# HDMI.net
KiCad netlist of a schematic drawn in Altium Designer
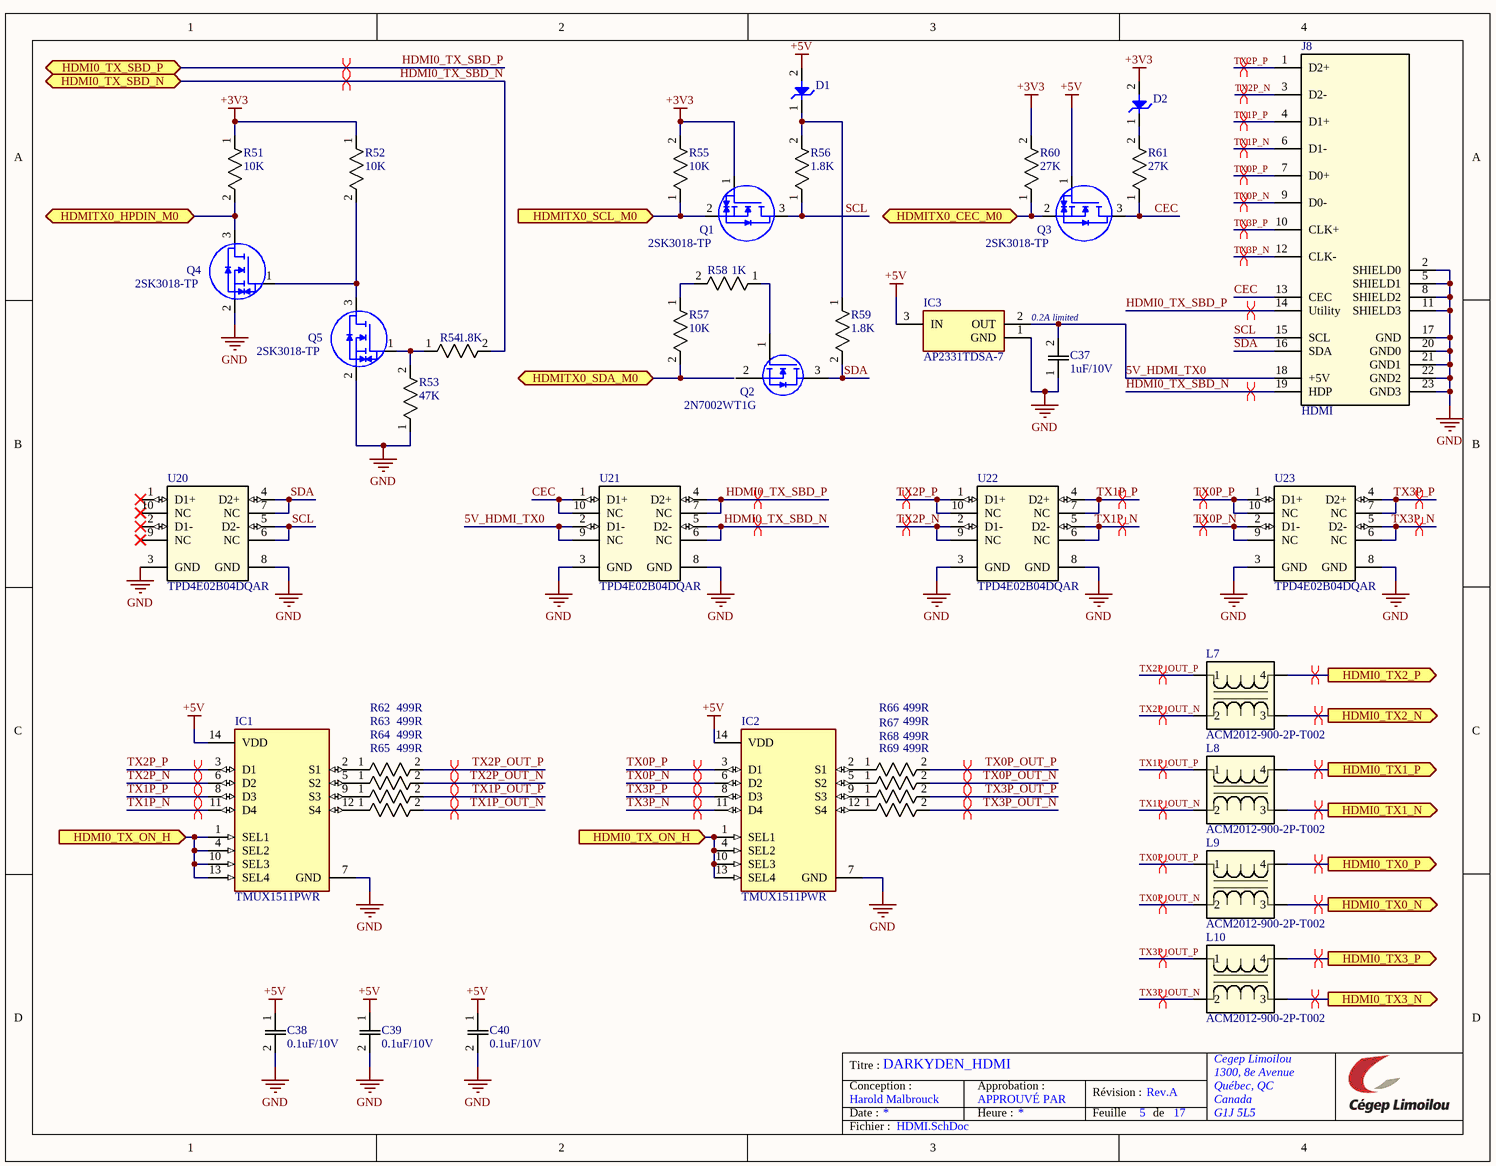
[diagram p0: HDMI.SchDoc]

(export (version "E")
  (design (tool "Eeschema 10.0.6"))
  (components
    (comp (ref "C37")
      (value "1uF/10V")
      (footprint "CAP_CC0805_YAG")
      (description "No Description Available")
      (libsource (lib "Capacitor_0805") (part "Capacitor_0805"))
    )
    (comp (ref "C38")
      (value "0.1uF/10V")
      (footprint "CAP_CC0805_YAG")
      (description "No Description Available")
      (libsource (lib "Capacitor_0805") (part "Capacitor_0805"))
    )
    (comp (ref "C39")
      (value "0.1uF/10V")
      (footprint "CAP_CC0805_YAG")
      (description "No Description Available")
      (libsource (lib "Capacitor_0805") (part "Capacitor_0805"))
    )
    (comp (ref "C40")
      (value "0.1uF/10V")
      (footprint "CAP_CC0805_YAG")
      (description "No Description Available")
      (libsource (lib "Capacitor_0805") (part "Capacitor_0805"))
    )
    (comp (ref "D1")
      (value "Schottky")
      (footprint "SamacSys:SODFL1608X70N")
      (description "DIODE SCHOTTKY 30V 200MA SOD523")
      (fields
        (field (name "MANUFACTURER_PART_NUMBER") "RB520S30T1G")
        (field (name "MOUSER PART NUMBER") "863-RB520S30T1G")
      )
      (libsource (lib "SamacSys") (part "Schottky"))
    )
    (comp (ref "D2")
      (value "Schottky")
      (footprint "SamacSys:SODFL1608X70N")
      (description "DIODE SCHOTTKY 30V 200MA SOD523")
      (fields
        (field (name "MANUFACTURER_PART_NUMBER") "RB520S30T1G")
        (field (name "MOUSER PART NUMBER") "863-RB520S30T1G")
      )
      (libsource (lib "SamacSys") (part "Schottky"))
    )
    (comp (ref "IC1")
      (value "TMUX1511PWR")
      (footprint "SamacSys:SOP65P640X120-14N")
      (description "Integrated Circuit")
      (fields (field (name "MOUSER PART NUMBER") "595-TMUX1511PWR"))
      (libsource (lib "SamacSys") (part "TMUX1511PWR"))
    )
    (comp (ref "IC2")
      (value "TMUX1511PWR")
      (footprint "SamacSys:SOP65P640X120-14N")
      (description "Integrated Circuit")
      (fields (field (name "MOUSER PART NUMBER") "595-TMUX1511PWR"))
      (libsource (lib "SamacSys") (part "TMUX1511PWR"))
    )
    (comp (ref "IC3")
      (value "AP2331TDSA-7")
      (footprint "SamacSys:SOT96P240X110-3N")
      (description "Integrated Circuit")
      (fields (field (name "MOUSER PART NUMBER") "621-AP2331TDSA-7"))
      (libsource (lib "SamacSys") (part "AP2331TDSA-7"))
    )
    (comp (ref "J8")
      (value "HDMI")
      (footprint "CONN19_2001-1-2-21-00-BK_CNC")
      (description "2001-1-2-21-00-BK")
      (libsource (lib "HDMI") (part "HDMI"))
    )
    (comp (ref "L7")
      (value "ACM2012-900-2P-T002")
      (footprint "ACM2012_TDK")
      (description "No Description Available")
      (libsource (lib "ACM2012") (part "ACM2012-900-2P-T002"))
    )
    (comp (ref "L8")
      (value "ACM2012-900-2P-T002")
      (footprint "ACM2012_TDK")
      (description "No Description Available")
      (libsource (lib "ACM2012") (part "ACM2012-900-2P-T002"))
    )
    (comp (ref "L9")
      (value "ACM2012-900-2P-T002")
      (footprint "ACM2012_TDK")
      (description "No Description Available")
      (libsource (lib "ACM2012") (part "ACM2012-900-2P-T002"))
    )
    (comp (ref "L10")
      (value "ACM2012-900-2P-T002")
      (footprint "ACM2012_TDK")
      (description "No Description Available")
      (libsource (lib "ACM2012") (part "ACM2012-900-2P-T002"))
    )
    (comp (ref "Q1")
      (value "2SK3018-TP")
      (footprint "SamacSys:SOT65P228X120-3N")
      (description "MOSFET (N-Channel)")
      (fields (field (name "MOUSER PART NUMBER") "833-2SK3018-TP"))
      (libsource (lib "SamacSys") (part "2SK3018-TP"))
    )
    (comp (ref "Q2")
      (value "2N7002WT1G")
      (footprint "SOT-323-3_2P2X1P35_ONS")
      (description "No Description Available")
      (libsource (lib "2N7002WT1G") (part "2N7002WT1G"))
    )
    (comp (ref "Q3")
      (value "2SK3018-TP")
      (footprint "SamacSys:SOT65P228X120-3N")
      (description "MOSFET (N-Channel)")
      (fields (field (name "MOUSER PART NUMBER") "833-2SK3018-TP"))
      (libsource (lib "SamacSys") (part "2SK3018-TP"))
    )
    (comp (ref "Q4")
      (value "2SK3018-TP")
      (footprint "SamacSys:SOT65P228X120-3N")
      (description "MOSFET (N-Channel)")
      (fields (field (name "MOUSER PART NUMBER") "833-2SK3018-TP"))
      (libsource (lib "SamacSys") (part "2SK3018-TP"))
    )
    (comp (ref "Q5")
      (value "2SK3018-TP")
      (footprint "SamacSys:SOT65P228X120-3N")
      (description "MOSFET (N-Channel)")
      (fields (field (name "MOUSER PART NUMBER") "833-2SK3018-TP"))
      (libsource (lib "SamacSys") (part "2SK3018-TP"))
    )
    (comp (ref "R51")
      (value "10K")
      (footprint "RES_0816_SUS")
      (description "No Description Available")
      (libsource (lib "RES_SMD_0603") (part "RG1608P-104-B-T5"))
    )
    (comp (ref "R52")
      (value "10K")
      (footprint "RES_0816_SUS")
      (description "No Description Available")
      (libsource (lib "RES_SMD_0603") (part "RG1608P-104-B-T5"))
    )
    (comp (ref "R53")
      (value "47K")
      (footprint "RES_0816_SUS")
      (description "No Description Available")
      (libsource (lib "RES_SMD_0603") (part "RG1608P-104-B-T5"))
    )
    (comp (ref "R54")
      (value "1.8K")
      (footprint "RES_0816_SUS")
      (description "No Description Available")
      (libsource (lib "RES_SMD_0603") (part "RG1608P-104-B-T5"))
    )
    (comp (ref "R55")
      (value "10K")
      (footprint "RES_0816_SUS")
      (description "No Description Available")
      (libsource (lib "RES_SMD_0603") (part "RG1608P-104-B-T5"))
    )
    (comp (ref "R56")
      (value "1.8K")
      (footprint "RES_0816_SUS")
      (description "No Description Available")
      (libsource (lib "RES_SMD_0603") (part "RG1608P-104-B-T5"))
    )
    (comp (ref "R57")
      (value "10K")
      (footprint "RES_0816_SUS")
      (description "No Description Available")
      (libsource (lib "RES_SMD_0603") (part "RG1608P-104-B-T5"))
    )
    (comp (ref "R58")
      (value "1K")
      (footprint "RES_0816_SUS")
      (description "No Description Available")
      (libsource (lib "RES_SMD_0603") (part "RG1608P-104-B-T5"))
    )
    (comp (ref "R59")
      (value "1.8K")
      (footprint "RES_0816_SUS")
      (description "No Description Available")
      (libsource (lib "RES_SMD_0603") (part "RG1608P-104-B-T5"))
    )
    (comp (ref "R60")
      (value "27K")
      (footprint "RES_0816_SUS")
      (description "No Description Available")
      (libsource (lib "RES_SMD_0603") (part "RG1608P-104-B-T5"))
    )
    (comp (ref "R61")
      (value "27K")
      (footprint "RES_0816_SUS")
      (description "No Description Available")
      (libsource (lib "RES_SMD_0603") (part "RG1608P-104-B-T5"))
    )
    (comp (ref "R62")
      (value "499R")
      (footprint "RES_0816_SUS")
      (description "No Description Available")
      (libsource (lib "RES_SMD_0603") (part "RG1608P-104-B-T5"))
    )
    (comp (ref "R63")
      (value "499R")
      (footprint "RES_0816_SUS")
      (description "No Description Available")
      (libsource (lib "RES_SMD_0603") (part "RG1608P-104-B-T5"))
    )
    (comp (ref "R64")
      (value "499R")
      (footprint "RES_0816_SUS")
      (description "No Description Available")
      (libsource (lib "RES_SMD_0603") (part "RG1608P-104-B-T5"))
    )
    (comp (ref "R65")
      (value "499R")
      (footprint "RES_0816_SUS")
      (description "No Description Available")
      (libsource (lib "RES_SMD_0603") (part "RG1608P-104-B-T5"))
    )
    (comp (ref "R66")
      (value "499R")
      (footprint "RES_0816_SUS")
      (description "No Description Available")
      (libsource (lib "RES_SMD_0603") (part "RG1608P-104-B-T5"))
    )
    (comp (ref "R67")
      (value "499R")
      (footprint "RES_0816_SUS")
      (description "No Description Available")
      (libsource (lib "RES_SMD_0603") (part "RG1608P-104-B-T5"))
    )
    (comp (ref "R68")
      (value "499R")
      (footprint "RES_0816_SUS")
      (description "No Description Available")
      (libsource (lib "RES_SMD_0603") (part "RG1608P-104-B-T5"))
    )
    (comp (ref "R69")
      (value "499R")
      (footprint "RES_0816_SUS")
      (description "No Description Available")
      (libsource (lib "RES_SMD_0603") (part "RG1608P-104-B-T5"))
    )
    (comp (ref "U20")
      (value "TPD4E02B04DQAR")
      (footprint "DQA0010A")
      (description "No Description Available")
      (fields (field (name "MANUFACTURER") "Texas Instruments"))
      (libsource (lib "TPD4E02B04DQAR") (part "TPD4E02B04DQAR"))
    )
    (comp (ref "U21")
      (value "TPD4E02B04DQAR")
      (footprint "DQA0010A")
      (description "No Description Available")
      (fields (field (name "MANUFACTURER") "Texas Instruments"))
      (libsource (lib "TPD4E02B04DQAR") (part "TPD4E02B04DQAR"))
    )
    (comp (ref "U22")
      (value "TPD4E02B04DQAR")
      (footprint "DQA0010A")
      (description "No Description Available")
      (fields (field (name "MANUFACTURER") "Texas Instruments"))
      (libsource (lib "TPD4E02B04DQAR") (part "TPD4E02B04DQAR"))
    )
    (comp (ref "U23")
      (value "TPD4E02B04DQAR")
      (footprint "DQA0010A")
      (description "No Description Available")
      (fields (field (name "MANUFACTURER") "Texas Instruments"))
      (libsource (lib "TPD4E02B04DQAR") (part "TPD4E02B04DQAR"))
    )
  )
  (nets
    (net (code "1") (name "+3V3") (class "Default")
      (node (ref "D2") (pin "2") (pinfunction "A_2") (pintype "passive"))
      (node (ref "Q1") (pin "1") (pinfunction "G_1") (pintype "passive"))
      (node (ref "R51") (pin "1") (pinfunction "1_1") (pintype "passive"))
      (node (ref "R52") (pin "1") (pinfunction "1_1") (pintype "passive"))
      (node (ref "R55") (pin "2") (pinfunction "2_2") (pintype "passive"))
      (node (ref "R60") (pin "2") (pinfunction "2_2") (pintype "passive"))
    )
    (net (code "2") (name "+5V") (class "Default")
      (node (ref "C38") (pin "1") (pinfunction "1_1") (pintype "passive"))
      (node (ref "C39") (pin "1") (pinfunction "1_1") (pintype "passive"))
      (node (ref "C40") (pin "1") (pinfunction "1_1") (pintype "passive"))
      (node (ref "D1") (pin "2") (pinfunction "A_2") (pintype "passive"))
      (node (ref "IC1") (pin "14") (pinfunction "VDD_14") (pintype "power_in"))
      (node (ref "IC2") (pin "14") (pinfunction "VDD_14") (pintype "power_in"))
      (node (ref "IC3") (pin "3") (pinfunction "IN_3") (pintype "passive"))
      (node (ref "Q3") (pin "1") (pinfunction "G_1") (pintype "passive"))
    )
    (net (code "3") (name "/5V_HDMI_TX0") (class "Default")
      (node (ref "C37") (pin "2") (pinfunction "2_2") (pintype "passive"))
      (node (ref "IC3") (pin "2") (pinfunction "OUT_2") (pintype "passive"))
      (node (ref "J8") (pin "18") (pinfunction "+5V_18") (pintype "passive"))
      (node (ref "U21") (pin "2") (pinfunction "D1-_2") (pintype "bidirectional"))
      (node (ref "U21") (pin "9") (pinfunction "NC_9") (pintype "passive"))
    )
    (net (code "4") (name "/CEC") (class "Default")
      (node (ref "J8") (pin "13") (pinfunction "CEC_13") (pintype "passive"))
      (node (ref "Q3") (pin "3") (pinfunction "D_3") (pintype "passive"))
      (node (ref "R61") (pin "1") (pinfunction "1_1") (pintype "passive"))
      (node (ref "U21") (pin "1") (pinfunction "D1+_1") (pintype "bidirectional"))
      (node (ref "U21") (pin "10") (pinfunction "NC_10") (pintype "passive"))
    )
    (net (code "5") (name "/HDMI0_TX0_N") (class "Default")
      (node (ref "L9") (pin "3") (pinfunction "3_3") (pintype "passive"))
    )
    (net (code "6") (name "/HDMI0_TX0_P") (class "Default")
      (node (ref "L9") (pin "4") (pinfunction "4_4") (pintype "passive"))
    )
    (net (code "7") (name "/HDMI0_TX1_N") (class "Default")
      (node (ref "L8") (pin "3") (pinfunction "3_3") (pintype "passive"))
    )
    (net (code "8") (name "/HDMI0_TX1_P") (class "Default")
      (node (ref "L8") (pin "4") (pinfunction "4_4") (pintype "passive"))
    )
    (net (code "9") (name "/HDMI0_TX2_N") (class "Default")
      (node (ref "L7") (pin "3") (pinfunction "3_3") (pintype "passive"))
    )
    (net (code "10") (name "/HDMI0_TX2_P") (class "Default")
      (node (ref "L7") (pin "4") (pinfunction "4_4") (pintype "passive"))
    )
    (net (code "11") (name "/HDMI0_TX3_N") (class "Default")
      (node (ref "L10") (pin "3") (pinfunction "3_3") (pintype "passive"))
    )
    (net (code "12") (name "/HDMI0_TX3_P") (class "Default")
      (node (ref "L10") (pin "4") (pinfunction "4_4") (pintype "passive"))
    )
    (net (code "13") (name "/HDMI0_TX_ON_H") (class "Default")
      (node (ref "IC1") (pin "1") (pinfunction "SEL1_1") (pintype "input"))
      (node (ref "IC1") (pin "10") (pinfunction "SEL3_10") (pintype "input"))
      (node (ref "IC1") (pin "13") (pinfunction "SEL4_13") (pintype "input"))
      (node (ref "IC1") (pin "4") (pinfunction "SEL2_4") (pintype "input"))
      (node (ref "IC2") (pin "1") (pinfunction "SEL1_1") (pintype "input"))
      (node (ref "IC2") (pin "10") (pinfunction "SEL3_10") (pintype "input"))
      (node (ref "IC2") (pin "13") (pinfunction "SEL4_13") (pintype "input"))
      (node (ref "IC2") (pin "4") (pinfunction "SEL2_4") (pintype "input"))
    )
    (net (code "14") (name "/HDMI0_TX_SBD_N") (class "Default")
      (node (ref "J8") (pin "19") (pinfunction "HDP_19") (pintype "passive"))
      (node (ref "R54") (pin "2") (pinfunction "2_2") (pintype "passive"))
      (node (ref "U21") (pin "5") (pinfunction "D2-_5") (pintype "bidirectional"))
      (node (ref "U21") (pin "6") (pinfunction "NC_6") (pintype "passive"))
    )
    (net (code "15") (name "/HDMI0_TX_SBD_P") (class "Default")
      (node (ref "J8") (pin "14") (pinfunction "Utility_14") (pintype "passive"))
      (node (ref "U21") (pin "4") (pinfunction "D2+_4") (pintype "bidirectional"))
      (node (ref "U21") (pin "7") (pinfunction "NC_7") (pintype "passive"))
    )
    (net (code "16") (name "/HDMITX0_CEC_M0") (class "Default")
      (node (ref "Q3") (pin "2") (pinfunction "S_2") (pintype "passive"))
      (node (ref "R60") (pin "1") (pinfunction "1_1") (pintype "passive"))
    )
    (net (code "17") (name "/HDMITX0_HPDIN_M0") (class "Default")
      (node (ref "Q4") (pin "3") (pinfunction "D_3") (pintype "passive"))
      (node (ref "R51") (pin "2") (pinfunction "2_2") (pintype "passive"))
    )
    (net (code "18") (name "/HDMITX0_SCL_M0") (class "Default")
      (node (ref "Q1") (pin "2") (pinfunction "S_2") (pintype "passive"))
      (node (ref "R55") (pin "1") (pinfunction "1_1") (pintype "passive"))
    )
    (net (code "19") (name "/HDMITX0_SDA_M0") (class "Default")
      (node (ref "R57") (pin "2") (pinfunction "2_2") (pintype "passive"))
    )
    (net (code "20") (name "/SCL") (class "Default")
      (node (ref "J8") (pin "15") (pinfunction "SCL_15") (pintype "passive"))
      (node (ref "Q1") (pin "3") (pinfunction "D_3") (pintype "passive"))
      (node (ref "R56") (pin "1") (pinfunction "1_1") (pintype "passive"))
      (node (ref "U20") (pin "5") (pinfunction "D2-_5") (pintype "bidirectional"))
      (node (ref "U20") (pin "6") (pinfunction "NC_6") (pintype "passive"))
    )
    (net (code "21") (name "/SDA") (class "Default")
      (node (ref "J8") (pin "16") (pinfunction "SDA_16") (pintype "passive"))
      (node (ref "Q2") (pin "3") (pinfunction "DRAIN_3") (pintype "passive"))
      (node (ref "R59") (pin "2") (pinfunction "2_2") (pintype "passive"))
      (node (ref "U20") (pin "4") (pinfunction "D2+_4") (pintype "bidirectional"))
      (node (ref "U20") (pin "7") (pinfunction "NC_7") (pintype "passive"))
    )
    (net (code "22") (name "/TX0P_N") (class "Default")
      (node (ref "IC2") (pin "6") (pinfunction "D2_6") (pintype "bidirectional"))
      (node (ref "J8") (pin "9") (pinfunction "D0-_9") (pintype "passive"))
      (node (ref "U23") (pin "2") (pinfunction "D1-_2") (pintype "bidirectional"))
      (node (ref "U23") (pin "9") (pinfunction "NC_9") (pintype "passive"))
    )
    (net (code "23") (name "/TX0P_OUT_N") (class "Default")
      (node (ref "L9") (pin "2") (pinfunction "2_2") (pintype "passive"))
      (node (ref "R67") (pin "2") (pinfunction "2_2") (pintype "passive"))
    )
    (net (code "24") (name "/TX0P_OUT_P") (class "Default")
      (node (ref "L9") (pin "1") (pinfunction "1_1") (pintype "passive"))
      (node (ref "R66") (pin "2") (pinfunction "2_2") (pintype "passive"))
    )
    (net (code "25") (name "/TX0P_P") (class "Default")
      (node (ref "IC2") (pin "3") (pinfunction "D1_3") (pintype "bidirectional"))
      (node (ref "J8") (pin "7") (pinfunction "D0+_7") (pintype "passive"))
      (node (ref "U23") (pin "1") (pinfunction "D1+_1") (pintype "bidirectional"))
      (node (ref "U23") (pin "10") (pinfunction "NC_10") (pintype "passive"))
    )
    (net (code "26") (name "/TX1P_N") (class "Default")
      (node (ref "IC1") (pin "11") (pinfunction "D4_11") (pintype "bidirectional"))
      (node (ref "J8") (pin "6") (pinfunction "D1-_6") (pintype "passive"))
      (node (ref "U22") (pin "5") (pinfunction "D2-_5") (pintype "bidirectional"))
      (node (ref "U22") (pin "6") (pinfunction "NC_6") (pintype "passive"))
    )
    (net (code "27") (name "/TX1P_OUT_N") (class "Default")
      (node (ref "L8") (pin "2") (pinfunction "2_2") (pintype "passive"))
      (node (ref "R65") (pin "2") (pinfunction "2_2") (pintype "passive"))
    )
    (net (code "28") (name "/TX1P_OUT_P") (class "Default")
      (node (ref "L8") (pin "1") (pinfunction "1_1") (pintype "passive"))
      (node (ref "R64") (pin "2") (pinfunction "2_2") (pintype "passive"))
    )
    (net (code "29") (name "/TX1P_P") (class "Default")
      (node (ref "IC1") (pin "8") (pinfunction "D3_8") (pintype "bidirectional"))
      (node (ref "J8") (pin "4") (pinfunction "D1+_4") (pintype "passive"))
      (node (ref "U22") (pin "4") (pinfunction "D2+_4") (pintype "bidirectional"))
      (node (ref "U22") (pin "7") (pinfunction "NC_7") (pintype "passive"))
    )
    (net (code "30") (name "/TX2P_N") (class "Default")
      (node (ref "IC1") (pin "6") (pinfunction "D2_6") (pintype "bidirectional"))
      (node (ref "J8") (pin "3") (pinfunction "D2-_3") (pintype "passive"))
      (node (ref "U22") (pin "2") (pinfunction "D1-_2") (pintype "bidirectional"))
      (node (ref "U22") (pin "9") (pinfunction "NC_9") (pintype "passive"))
    )
    (net (code "31") (name "/TX2P_OUT_N") (class "Default")
      (node (ref "L7") (pin "2") (pinfunction "2_2") (pintype "passive"))
      (node (ref "R63") (pin "2") (pinfunction "2_2") (pintype "passive"))
    )
    (net (code "32") (name "/TX2P_OUT_P") (class "Default")
      (node (ref "L7") (pin "1") (pinfunction "1_1") (pintype "passive"))
      (node (ref "R62") (pin "2") (pinfunction "2_2") (pintype "passive"))
    )
    (net (code "33") (name "/TX2P_P") (class "Default")
      (node (ref "IC1") (pin "3") (pinfunction "D1_3") (pintype "bidirectional"))
      (node (ref "J8") (pin "1") (pinfunction "D2+_1") (pintype "passive"))
      (node (ref "U22") (pin "1") (pinfunction "D1+_1") (pintype "bidirectional"))
      (node (ref "U22") (pin "10") (pinfunction "NC_10") (pintype "passive"))
    )
    (net (code "34") (name "/TX3P_N") (class "Default")
      (node (ref "IC2") (pin "11") (pinfunction "D4_11") (pintype "bidirectional"))
      (node (ref "J8") (pin "12") (pinfunction "CLK-_12") (pintype "passive"))
      (node (ref "U23") (pin "5") (pinfunction "D2-_5") (pintype "bidirectional"))
      (node (ref "U23") (pin "6") (pinfunction "NC_6") (pintype "passive"))
    )
    (net (code "35") (name "/TX3P_OUT_N") (class "Default")
      (node (ref "L10") (pin "2") (pinfunction "2_2") (pintype "passive"))
      (node (ref "R69") (pin "2") (pinfunction "2_2") (pintype "passive"))
    )
    (net (code "36") (name "/TX3P_OUT_P") (class "Default")
      (node (ref "L10") (pin "1") (pinfunction "1_1") (pintype "passive"))
      (node (ref "R68") (pin "2") (pinfunction "2_2") (pintype "passive"))
    )
    (net (code "37") (name "/TX3P_P") (class "Default")
      (node (ref "IC2") (pin "8") (pinfunction "D3_8") (pintype "bidirectional"))
      (node (ref "J8") (pin "10") (pinfunction "CLK+_10") (pintype "passive"))
      (node (ref "U23") (pin "4") (pinfunction "D2+_4") (pintype "bidirectional"))
      (node (ref "U23") (pin "7") (pinfunction "NC_7") (pintype "passive"))
    )
    (net (code "38") (name "GND") (class "Default")
      (node (ref "C37") (pin "1") (pinfunction "1_1") (pintype "passive"))
      (node (ref "C38") (pin "2") (pinfunction "2_2") (pintype "passive"))
      (node (ref "C39") (pin "2") (pinfunction "2_2") (pintype "passive"))
      (node (ref "C40") (pin "2") (pinfunction "2_2") (pintype "passive"))
      (node (ref "IC1") (pin "7") (pinfunction "GND_7") (pintype "power_in"))
      (node (ref "IC2") (pin "7") (pinfunction "GND_7") (pintype "power_in"))
      (node (ref "IC3") (pin "1") (pinfunction "GND_1") (pintype "passive"))
      (node (ref "J8") (pin "11") (pinfunction "SHIELD3_11") (pintype "passive"))
      (node (ref "J8") (pin "17") (pinfunction "GND_17") (pintype "passive"))
      (node (ref "J8") (pin "2") (pinfunction "SHIELD0_2") (pintype "passive"))
      (node (ref "J8") (pin "20") (pinfunction "GND0_20") (pintype "passive"))
      (node (ref "J8") (pin "21") (pinfunction "GND1_21") (pintype "passive"))
      (node (ref "J8") (pin "22") (pinfunction "GND2_22") (pintype "passive"))
      (node (ref "J8") (pin "23") (pinfunction "GND3_23") (pintype "passive"))
      (node (ref "J8") (pin "5") (pinfunction "SHIELD1_5") (pintype "passive"))
      (node (ref "J8") (pin "8") (pinfunction "SHIELD2_8") (pintype "passive"))
      (node (ref "Q4") (pin "2") (pinfunction "S_2") (pintype "passive"))
      (node (ref "Q5") (pin "2") (pinfunction "S_2") (pintype "passive"))
      (node (ref "R53") (pin "1") (pinfunction "1_1") (pintype "passive"))
      (node (ref "U20") (pin "3") (pinfunction "GND_3") (pintype "passive"))
      (node (ref "U20") (pin "8") (pinfunction "GND_8") (pintype "passive"))
      (node (ref "U21") (pin "3") (pinfunction "GND_3") (pintype "passive"))
      (node (ref "U21") (pin "8") (pinfunction "GND_8") (pintype "passive"))
      (node (ref "U22") (pin "3") (pinfunction "GND_3") (pintype "passive"))
      (node (ref "U22") (pin "8") (pinfunction "GND_8") (pintype "passive"))
      (node (ref "U23") (pin "3") (pinfunction "GND_3") (pintype "passive"))
      (node (ref "U23") (pin "8") (pinfunction "GND_8") (pintype "passive"))
    )
    (net (code "39") (name "Net-(D1-K)") (class "Default")
      (node (ref "D1") (pin "1") (pinfunction "K_1") (pintype "passive"))
      (node (ref "R56") (pin "2") (pinfunction "2_2") (pintype "passive"))
      (node (ref "R59") (pin "1") (pinfunction "1_1") (pintype "passive"))
    )
    (net (code "40") (name "Net-(D2-K)") (class "Default")
      (node (ref "D2") (pin "1") (pinfunction "K_1") (pintype "passive"))
      (node (ref "R61") (pin "2") (pinfunction "2_2") (pintype "passive"))
    )
    (net (code "41") (name "Net-(IC1-S1)") (class "Default")
      (node (ref "IC1") (pin "2") (pinfunction "S1_2") (pintype "bidirectional"))
      (node (ref "R62") (pin "1") (pinfunction "1_1") (pintype "passive"))
    )
    (net (code "42") (name "Net-(IC1-S2)") (class "Default")
      (node (ref "IC1") (pin "5") (pinfunction "S2_5") (pintype "bidirectional"))
      (node (ref "R63") (pin "1") (pinfunction "1_1") (pintype "passive"))
    )
    (net (code "43") (name "Net-(IC1-S3)") (class "Default")
      (node (ref "IC1") (pin "9") (pinfunction "S3_9") (pintype "bidirectional"))
      (node (ref "R64") (pin "1") (pinfunction "1_1") (pintype "passive"))
    )
    (net (code "44") (name "Net-(IC1-S4)") (class "Default")
      (node (ref "IC1") (pin "12") (pinfunction "S4_12") (pintype "bidirectional"))
      (node (ref "R65") (pin "1") (pinfunction "1_1") (pintype "passive"))
    )
    (net (code "45") (name "Net-(IC2-S1)") (class "Default")
      (node (ref "IC2") (pin "2") (pinfunction "S1_2") (pintype "bidirectional"))
      (node (ref "R66") (pin "1") (pinfunction "1_1") (pintype "passive"))
    )
    (net (code "46") (name "Net-(IC2-S2)") (class "Default")
      (node (ref "IC2") (pin "5") (pinfunction "S2_5") (pintype "bidirectional"))
      (node (ref "R67") (pin "1") (pinfunction "1_1") (pintype "passive"))
    )
    (net (code "47") (name "Net-(IC2-S3)") (class "Default")
      (node (ref "IC2") (pin "9") (pinfunction "S3_9") (pintype "bidirectional"))
      (node (ref "R68") (pin "1") (pinfunction "1_1") (pintype "passive"))
    )
    (net (code "48") (name "Net-(IC2-S4)") (class "Default")
      (node (ref "IC2") (pin "12") (pinfunction "S4_12") (pintype "bidirectional"))
      (node (ref "R69") (pin "1") (pinfunction "1_1") (pintype "passive"))
    )
    (net (code "49") (name "Net-(Q2-GATE)") (class "Default")
      (node (ref "Q2") (pin "1") (pinfunction "GATE_1") (pintype "passive"))
      (node (ref "R58") (pin "1") (pinfunction "1_1") (pintype "passive"))
    )
    (net (code "50") (name "Net-(Q4-G)") (class "Default")
      (node (ref "Q4") (pin "1") (pinfunction "G_1") (pintype "passive"))
      (node (ref "Q5") (pin "3") (pinfunction "D_3") (pintype "passive"))
      (node (ref "R52") (pin "2") (pinfunction "2_2") (pintype "passive"))
    )
    (net (code "51") (name "Net-(Q5-G)") (class "Default")
      (node (ref "Q5") (pin "1") (pinfunction "G_1") (pintype "passive"))
      (node (ref "R53") (pin "2") (pinfunction "2_2") (pintype "passive"))
      (node (ref "R54") (pin "1") (pinfunction "1_1") (pintype "passive"))
    )
    (net (code "52") (name "Net-(R57-Pad1)") (class "Default")
      (node (ref "R57") (pin "1") (pinfunction "1_1") (pintype "passive"))
      (node (ref "R58") (pin "2") (pinfunction "2_2") (pintype "passive"))
    )
    (net (code "53") (name "unconnected-(Q2-SOURCE-Pad2)") (class "Default")
      (node (ref "Q2") (pin "2") (pinfunction "SOURCE_2") (pintype "passive"))
    )
    (net (code "54") (name "unconnected-(U20-D1+-Pad1)") (class "Default")
      (node (ref "U20") (pin "1") (pinfunction "D1+_1") (pintype "bidirectional+no_connect"))
    )
    (net (code "55") (name "unconnected-(U20-D1--Pad2)") (class "Default")
      (node (ref "U20") (pin "2") (pinfunction "D1-_2") (pintype "bidirectional+no_connect"))
    )
    (net (code "56") (name "unconnected-(U20-NC-Pad9)") (class "Default")
      (node (ref "U20") (pin "9") (pinfunction "NC_9") (pintype "passive+no_connect"))
    )
    (net (code "57") (name "unconnected-(U20-NC-Pad10)") (class "Default")
      (node (ref "U20") (pin "10") (pinfunction "NC_10") (pintype "passive+no_connect"))
    )
  )
)
